# Power_Regulation.net
KiCad netlist of a schematic drawn in Altium Designer
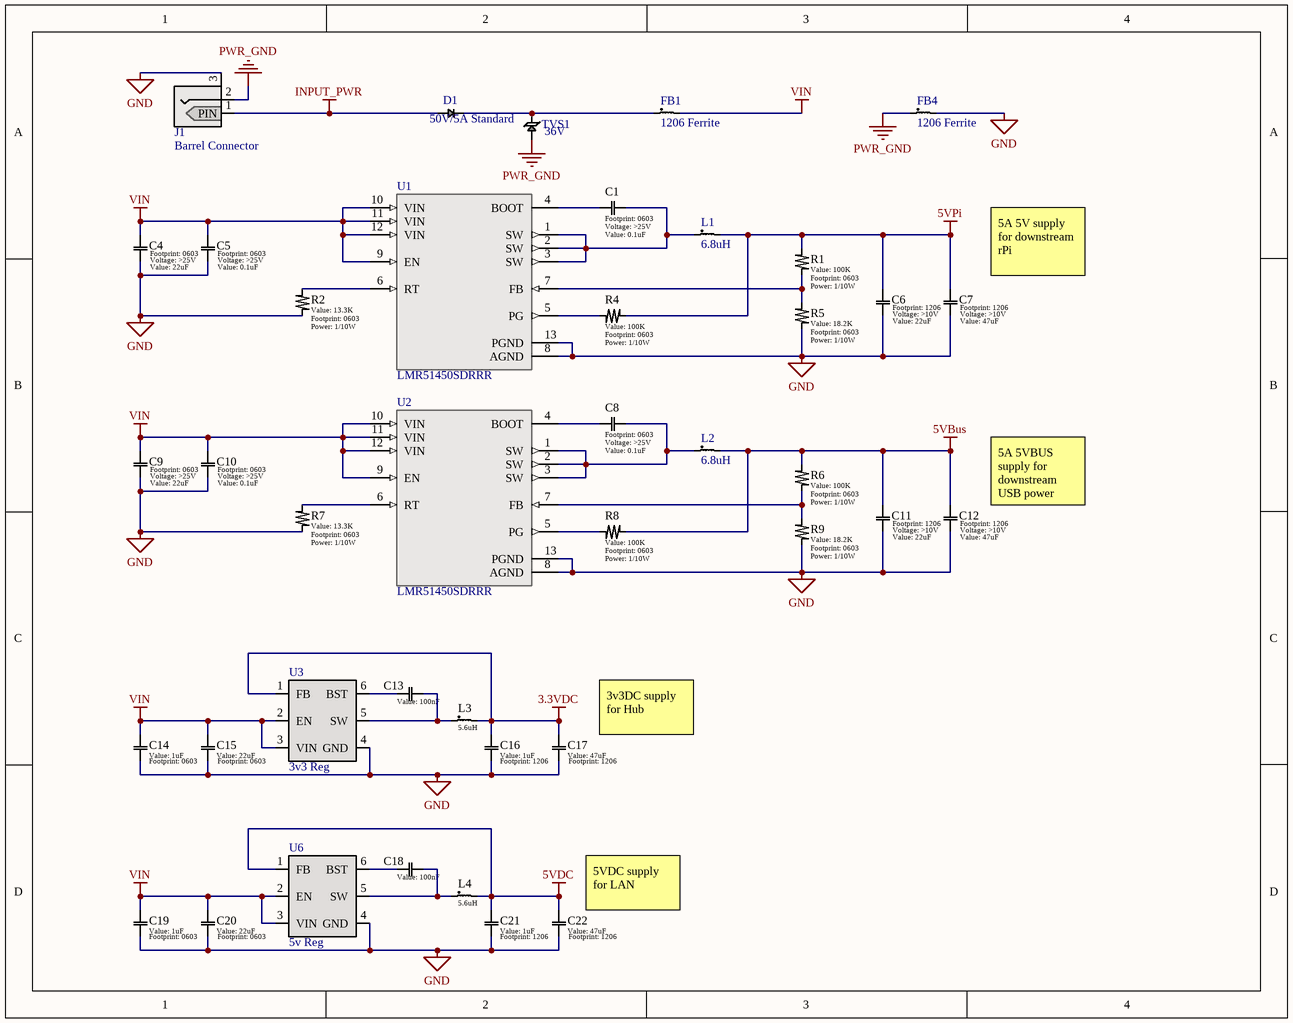
[diagram p0: Power Regulation.SchDoc]

(export (version "E")
  (design (tool "Eeschema 10.0.6"))
  (components
    (comp (ref "C1")
      (value "0.1uF")
      (footprint "0603")
      (fields
        (field (name "VOLTAGE") ">25V")
        (field (name "TOLERANCE") "10%")
        (field (name "Comment") "Generic Capacitor")
      )
      (libsource (lib "Capacitors") (part "Generic Capacitor"))
    )
    (comp (ref "C4")
      (value "22uF")
      (footprint "0603")
      (fields
        (field (name "VOLTAGE") ">25V")
        (field (name "TOLERANCE") "10%")
        (field (name "Comment") "Generic Capacitor")
      )
      (libsource (lib "Capacitors") (part "Generic Capacitor"))
    )
    (comp (ref "C5")
      (value "0.1uF")
      (footprint "0603")
      (fields
        (field (name "VOLTAGE") ">25V")
        (field (name "TOLERANCE") "10%")
        (field (name "Comment") "Generic Capacitor")
      )
      (libsource (lib "Capacitors") (part "Generic Capacitor"))
    )
    (comp (ref "C6")
      (value "22uF")
      (footprint "1206")
      (fields
        (field (name "VOLTAGE") ">10V")
        (field (name "TOLERANCE") "20%")
        (field (name "Comment") "Generic Capacitor")
      )
      (libsource (lib "Capacitors") (part "Generic Capacitor"))
    )
    (comp (ref "C7")
      (value "47uF")
      (footprint "1206")
      (fields
        (field (name "VOLTAGE") ">10V")
        (field (name "TOLERANCE") "10%")
        (field (name "Comment") "Generic Capacitor")
      )
      (libsource (lib "Capacitors") (part "Generic Capacitor"))
    )
    (comp (ref "C8")
      (value "0.1uF")
      (footprint "0603")
      (fields
        (field (name "VOLTAGE") ">25V")
        (field (name "TOLERANCE") "10%")
        (field (name "Comment") "Generic Capacitor")
      )
      (libsource (lib "Capacitors") (part "Generic Capacitor"))
    )
    (comp (ref "C9")
      (value "22uF")
      (footprint "0603")
      (fields
        (field (name "VOLTAGE") ">25V")
        (field (name "TOLERANCE") "10%")
        (field (name "Comment") "Generic Capacitor")
      )
      (libsource (lib "Capacitors") (part "Generic Capacitor"))
    )
    (comp (ref "C10")
      (value "0.1uF")
      (footprint "0603")
      (fields
        (field (name "VOLTAGE") ">25V")
        (field (name "TOLERANCE") "10%")
        (field (name "Comment") "Generic Capacitor")
      )
      (libsource (lib "Capacitors") (part "Generic Capacitor"))
    )
    (comp (ref "C11")
      (value "22uF")
      (footprint "1206")
      (fields
        (field (name "VOLTAGE") ">10V")
        (field (name "TOLERANCE") "20%")
        (field (name "Comment") "Generic Capacitor")
      )
      (libsource (lib "Capacitors") (part "Generic Capacitor"))
    )
    (comp (ref "C12")
      (value "47uF")
      (footprint "1206")
      (fields
        (field (name "VOLTAGE") ">10V")
        (field (name "TOLERANCE") "10%")
        (field (name "Comment") "Generic Capacitor")
      )
      (libsource (lib "Capacitors") (part "Generic Capacitor"))
    )
    (comp (ref "C13")
      (value "100nF")
      (footprint "0603")
      (fields
        (field (name "VOLTAGE") ">10V")
        (field (name "TOLERANCE") "10%")
        (field (name "Comment") "Generic Capacitor")
      )
      (libsource (lib "Capacitors") (part "Generic Capacitor"))
    )
    (comp (ref "C14")
      (value "1uF")
      (footprint "0603")
      (fields
        (field (name "VOLTAGE") ">10V")
        (field (name "TOLERANCE") "10%")
        (field (name "Comment") "Generic Capacitor")
      )
      (libsource (lib "Capacitors") (part "Generic Capacitor"))
    )
    (comp (ref "C15")
      (value "22uF")
      (footprint "0603")
      (fields
        (field (name "VOLTAGE") ">10V")
        (field (name "TOLERANCE") "10%")
        (field (name "Comment") "Generic Capacitor")
      )
      (libsource (lib "Capacitors") (part "Generic Capacitor"))
    )
    (comp (ref "C16")
      (value "1uF")
      (footprint "1206")
      (fields
        (field (name "VOLTAGE") ">10V")
        (field (name "TOLERANCE") "10%")
        (field (name "Comment") "Generic Capacitor")
      )
      (libsource (lib "Capacitors") (part "Generic Capacitor"))
    )
    (comp (ref "C17")
      (value "47uF")
      (footprint "1206")
      (fields
        (field (name "VOLTAGE") ">10V")
        (field (name "TOLERANCE") "10%")
        (field (name "Comment") "Generic Capacitor")
      )
      (libsource (lib "Capacitors") (part "Generic Capacitor"))
    )
    (comp (ref "C18")
      (value "100nF")
      (footprint "0603")
      (fields
        (field (name "VOLTAGE") ">10V")
        (field (name "TOLERANCE") "10%")
        (field (name "Comment") "Generic Capacitor")
      )
      (libsource (lib "Capacitors") (part "Generic Capacitor"))
    )
    (comp (ref "C19")
      (value "1uF")
      (footprint "0603")
      (fields
        (field (name "VOLTAGE") ">10V")
        (field (name "TOLERANCE") "10%")
        (field (name "Comment") "Generic Capacitor")
      )
      (libsource (lib "Capacitors") (part "Generic Capacitor"))
    )
    (comp (ref "C20")
      (value "22uF")
      (footprint "0603")
      (fields
        (field (name "VOLTAGE") ">10V")
        (field (name "TOLERANCE") "10%")
        (field (name "Comment") "Generic Capacitor")
      )
      (libsource (lib "Capacitors") (part "Generic Capacitor"))
    )
    (comp (ref "C21")
      (value "1uF")
      (footprint "1206")
      (fields
        (field (name "VOLTAGE") ">10V")
        (field (name "TOLERANCE") "10%")
        (field (name "Comment") "Generic Capacitor")
      )
      (libsource (lib "Capacitors") (part "Generic Capacitor"))
    )
    (comp (ref "C22")
      (value "47uF")
      (footprint "1206")
      (fields
        (field (name "VOLTAGE") ">10V")
        (field (name "TOLERANCE") "10%")
        (field (name "Comment") "Generic Capacitor")
      )
      (libsource (lib "Capacitors") (part "Generic Capacitor"))
    )
    (comp (ref "D1")
      (value "50V/5A Standard")
      (footprint "DO-214AC")
      (description "Diode Super Barrier 50V 5A Surface Mount")
      (libsource (lib "Diodes") (part "SBRT5A50SA-13"))
    )
    (comp (ref "FB1")
      (value "1206 Ferrite")
      (footprint "1206")
      (description "160 Ohms @ 100MHz 1 Power, Signal Line Ferrite Bead 1206 (3216 Metric) 6A 18mOhm")
      (libsource (lib "Inductors") (part "HI1206T161R-10"))
    )
    (comp (ref "FB4")
      (value "1206 Ferrite")
      (footprint "1206")
      (description "160 Ohms @ 100MHz 1 Power, Signal Line Ferrite Bead 1206 (3216 Metric) 6A 18mOhm")
      (libsource (lib "Inductors") (part "HI1206T161R-10"))
    )
    (comp (ref "J1")
      (value "Barrel Connector")
      (footprint "PJ-082BH")
      (description "CONN PWR JACK 2.5X5.5MM SOLDER")
      (libsource (lib "Connectors") (part "PJ-082BH"))
    )
    (comp (ref "L1")
      (value "6.8uH")
      (footprint "IHLP3232DZER6R8M11")
      (description "FIXED IND 6.8UH 7A 33.4 MOHM SMD")
      (fields (field (name "TOLERANCE") "20%") (field (name "INDUCTANCE") "6.8uH"))
      (libsource (lib "Inductors") (part "IHLP3232DZER6R8M11"))
    )
    (comp (ref "L2")
      (value "6.8uH")
      (footprint "IHLP3232DZER6R8M11")
      (description "FIXED IND 6.8UH 7A 33.4 MOHM SMD")
      (fields (field (name "TOLERANCE") "20%") (field (name "INDUCTANCE") "6.8uH"))
      (libsource (lib "Inductors") (part "IHLP3232DZER6R8M11"))
    )
    (comp (ref "L3")
      (value "5.6uH")
      (footprint "TMPC0402HP")
      (description "2A 5.6uH ±20% SMD Power Inductor")
      (libsource (lib "Inductors") (part "TMPC0402HP-5R6MG-Z02"))
    )
    (comp (ref "L4")
      (value "5.6uH")
      (footprint "TMPC0402HP")
      (description "2A 5.6uH ±20% SMD Power Inductor")
      (libsource (lib "Inductors") (part "TMPC0402HP-5R6MG-Z02"))
    )
    (comp (ref "R1")
      (value "100K")
      (footprint "0603")
      (fields
        (field (name "TOLERANCE") "1%")
        (field (name "POWER") "1/10W")
        (field (name "Comment") "Generic Resistor")
      )
      (libsource (lib "Resistors") (part "Generic Resistor"))
    )
    (comp (ref "R2")
      (value "13.3K")
      (footprint "0603")
      (fields
        (field (name "TOLERANCE") "1%")
        (field (name "POWER") "1/10W")
        (field (name "Comment") "Generic Resistor")
      )
      (libsource (lib "Resistors") (part "Generic Resistor"))
    )
    (comp (ref "R4")
      (value "100K")
      (footprint "0603")
      (fields
        (field (name "TOLERANCE") "1%")
        (field (name "POWER") "1/10W")
        (field (name "Comment") "Generic Resistor")
      )
      (libsource (lib "Resistors") (part "Generic Resistor"))
    )
    (comp (ref "R5")
      (value "18.2K")
      (footprint "0603")
      (fields
        (field (name "TOLERANCE") "1%")
        (field (name "POWER") "1/10W")
        (field (name "Comment") "Generic Resistor")
      )
      (libsource (lib "Resistors") (part "Generic Resistor"))
    )
    (comp (ref "R6")
      (value "100K")
      (footprint "0603")
      (fields
        (field (name "TOLERANCE") "1%")
        (field (name "POWER") "1/10W")
        (field (name "Comment") "Generic Resistor")
      )
      (libsource (lib "Resistors") (part "Generic Resistor"))
    )
    (comp (ref "R7")
      (value "13.3K")
      (footprint "0603")
      (fields
        (field (name "TOLERANCE") "1%")
        (field (name "POWER") "1/10W")
        (field (name "Comment") "Generic Resistor")
      )
      (libsource (lib "Resistors") (part "Generic Resistor"))
    )
    (comp (ref "R8")
      (value "100K")
      (footprint "0603")
      (fields
        (field (name "TOLERANCE") "1%")
        (field (name "POWER") "1/10W")
        (field (name "Comment") "Generic Resistor")
      )
      (libsource (lib "Resistors") (part "Generic Resistor"))
    )
    (comp (ref "R9")
      (value "18.2K")
      (footprint "0603")
      (fields
        (field (name "TOLERANCE") "1%")
        (field (name "POWER") "1/10W")
        (field (name "Comment") "Generic Resistor")
      )
      (libsource (lib "Resistors") (part "Generic Resistor"))
    )
    (comp (ref "TVS1")
      (value "36V")
      (footprint "DO-214AC")
      (description "58.1V Clamp 6.9A Ipp Tvs Diode Surface Mount DO-214AC (SMA)")
      (libsource (lib "Diodes") (part "SMAJ36A"))
    )
    (comp (ref "U1")
      (value "LMR51450SDRRR")
      (footprint "WSON-12")
      (description "36-V, 5-A synchronous buck converter")
      (fields (field (name "MF") "Texas Instruments"))
      (libsource (lib "Regulators") (part "LMR51450SDRRR"))
    )
    (comp (ref "U2")
      (value "LMR51450SDRRR")
      (footprint "WSON-12")
      (description "36-V, 5-A synchronous buck converter")
      (fields (field (name "MF") "Texas Instruments"))
      (libsource (lib "Regulators") (part "LMR51450SDRRR"))
    )
    (comp (ref "U3")
      (value "3v3 Reg")
      (footprint "TSOT-23-6")
      (description "Switching Voltage Regulators DCDC Conv HV Buck TSOT26 T&R 3K")
      (fields
        (field (name "MANUFACTURER_PART_NUMBER") "AP63203WU-7")
        (field (name "MOUSER PART NUMBER") "621-AP63203WU-7")
      )
      (libsource (lib "Regulators") (part "AP63203WU-7"))
    )
    (comp (ref "U6")
      (value "5v Reg")
      (footprint "TSOT-23-6")
      (description "Step-down type Fixed 2A 5V 3.8V~32V")
      (fields
        (field (name "MANUFACTURER_PART_NUMBER") "AP63205WU-7")
        (field (name "COPYRIGHT") "Copyright (C) 2023 Ultra Librarian. All rights reserved.")
      )
      (libsource (lib "Regulators") (part "AP63205WU-7"))
    )
  )
  (nets
    (net (code "1") (name "3.3VDC") (class "Default")
      (node (ref "C16") (pin "1") (pinfunction "1_1") (pintype "passive"))
      (node (ref "C17") (pin "1") (pinfunction "1_1") (pintype "passive"))
      (node (ref "L3") (pin "2") (pinfunction "2_2") (pintype "passive"))
      (node (ref "U3") (pin "1") (pinfunction "FB_1") (pintype "passive"))
    )
    (net (code "2") (name "5VBus") (class "Default")
      (node (ref "C11") (pin "1") (pinfunction "1_1") (pintype "passive"))
      (node (ref "C12") (pin "1") (pinfunction "1_1") (pintype "passive"))
      (node (ref "L2") (pin "2") (pinfunction "2_2") (pintype "passive"))
      (node (ref "R6") (pin "2") (pinfunction "2_2") (pintype "passive"))
      (node (ref "R8") (pin "1") (pinfunction "1_1") (pintype "passive"))
    )
    (net (code "3") (name "5VDC") (class "Default")
      (node (ref "C21") (pin "1") (pinfunction "1_1") (pintype "passive"))
      (node (ref "C22") (pin "1") (pinfunction "1_1") (pintype "passive"))
      (node (ref "L4") (pin "2") (pinfunction "2_2") (pintype "passive"))
      (node (ref "U6") (pin "1") (pinfunction "FB_1") (pintype "passive"))
    )
    (net (code "4") (name "5VPi") (class "Default")
      (node (ref "C6") (pin "1") (pinfunction "1_1") (pintype "passive"))
      (node (ref "C7") (pin "1") (pinfunction "1_1") (pintype "passive"))
      (node (ref "L1") (pin "2") (pinfunction "2_2") (pintype "passive"))
      (node (ref "R1") (pin "2") (pinfunction "2_2") (pintype "passive"))
      (node (ref "R4") (pin "1") (pinfunction "1_1") (pintype "passive"))
    )
    (net (code "5") (name "GND") (class "Default")
      (node (ref "C10") (pin "2") (pinfunction "2_2") (pintype "passive"))
      (node (ref "C11") (pin "2") (pinfunction "2_2") (pintype "passive"))
      (node (ref "C12") (pin "2") (pinfunction "2_2") (pintype "passive"))
      (node (ref "C14") (pin "2") (pinfunction "2_2") (pintype "passive"))
      (node (ref "C15") (pin "2") (pinfunction "2_2") (pintype "passive"))
      (node (ref "C16") (pin "2") (pinfunction "2_2") (pintype "passive"))
      (node (ref "C17") (pin "2") (pinfunction "2_2") (pintype "passive"))
      (node (ref "C19") (pin "2") (pinfunction "2_2") (pintype "passive"))
      (node (ref "C20") (pin "2") (pinfunction "2_2") (pintype "passive"))
      (node (ref "C21") (pin "2") (pinfunction "2_2") (pintype "passive"))
      (node (ref "C22") (pin "2") (pinfunction "2_2") (pintype "passive"))
      (node (ref "C4") (pin "2") (pinfunction "2_2") (pintype "passive"))
      (node (ref "C5") (pin "2") (pinfunction "2_2") (pintype "passive"))
      (node (ref "C6") (pin "2") (pinfunction "2_2") (pintype "passive"))
      (node (ref "C7") (pin "2") (pinfunction "2_2") (pintype "passive"))
      (node (ref "C9") (pin "2") (pinfunction "2_2") (pintype "passive"))
      (node (ref "FB4") (pin "2") (pinfunction "2_2") (pintype "passive"))
      (node (ref "J1") (pin "3") (pinfunction "SHD_B_3") (pintype "passive"))
      (node (ref "R2") (pin "1") (pinfunction "1_1") (pintype "passive"))
      (node (ref "R5") (pin "1") (pinfunction "1_1") (pintype "passive"))
      (node (ref "R7") (pin "1") (pinfunction "1_1") (pintype "passive"))
      (node (ref "R9") (pin "1") (pinfunction "1_1") (pintype "passive"))
      (node (ref "U1") (pin "13") (pinfunction "PGND_13") (pintype "power_in"))
      (node (ref "U1") (pin "8") (pinfunction "AGND_8") (pintype "power_in"))
      (node (ref "U2") (pin "13") (pinfunction "PGND_13") (pintype "power_in"))
      (node (ref "U2") (pin "8") (pinfunction "AGND_8") (pintype "power_in"))
      (node (ref "U3") (pin "4") (pinfunction "GND_4") (pintype "power_in"))
      (node (ref "U6") (pin "4") (pinfunction "GND_4") (pintype "power_in"))
    )
    (net (code "6") (name "INPUT_PWR") (class "Default")
      (node (ref "D1") (pin "2") (pinfunction "Anode_2") (pintype "passive"))
      (node (ref "J1") (pin "1") (pinfunction "PIN_1") (pintype "passive"))
    )
    (net (code "7") (name "Net-(C1-Pad2)") (class "Default")
      (node (ref "C1") (pin "2") (pinfunction "2_2") (pintype "passive"))
      (node (ref "L1") (pin "1") (pinfunction "1_1") (pintype "passive"))
      (node (ref "U1") (pin "1") (pinfunction "SW_1") (pintype "output"))
      (node (ref "U1") (pin "2") (pinfunction "SW_2") (pintype "output"))
      (node (ref "U1") (pin "3") (pinfunction "SW_3") (pintype "output"))
    )
    (net (code "8") (name "Net-(C8-Pad2)") (class "Default")
      (node (ref "C8") (pin "2") (pinfunction "2_2") (pintype "passive"))
      (node (ref "L2") (pin "1") (pinfunction "1_1") (pintype "passive"))
      (node (ref "U2") (pin "1") (pinfunction "SW_1") (pintype "output"))
      (node (ref "U2") (pin "2") (pinfunction "SW_2") (pintype "output"))
      (node (ref "U2") (pin "3") (pinfunction "SW_3") (pintype "output"))
    )
    (net (code "9") (name "Net-(D1-Cathode)") (class "Default")
      (node (ref "D1") (pin "1") (pinfunction "Cathode_1") (pintype "passive"))
      (node (ref "FB1") (pin "1") (pinfunction "1_1") (pintype "passive"))
      (node (ref "TVS1") (pin "1") (pinfunction "Cathode_1") (pintype "passive"))
    )
    (net (code "10") (name "Net-(U1-BOOT)") (class "Default")
      (node (ref "C1") (pin "1") (pinfunction "1_1") (pintype "passive"))
      (node (ref "U1") (pin "4") (pinfunction "BOOT_4") (pintype "passive"))
    )
    (net (code "11") (name "Net-(U1-FB)") (class "Default")
      (node (ref "R1") (pin "1") (pinfunction "1_1") (pintype "passive"))
      (node (ref "R5") (pin "2") (pinfunction "2_2") (pintype "passive"))
      (node (ref "U1") (pin "7") (pinfunction "FB_7") (pintype "input"))
    )
    (net (code "12") (name "Net-(U1-PG)") (class "Default")
      (node (ref "R4") (pin "2") (pinfunction "2_2") (pintype "passive"))
      (node (ref "U1") (pin "5") (pinfunction "PG_5") (pintype "output"))
    )
    (net (code "13") (name "Net-(U1-RT)") (class "Default")
      (node (ref "R2") (pin "2") (pinfunction "2_2") (pintype "passive"))
      (node (ref "U1") (pin "6") (pinfunction "RT_6") (pintype "input"))
    )
    (net (code "14") (name "Net-(U2-BOOT)") (class "Default")
      (node (ref "C8") (pin "1") (pinfunction "1_1") (pintype "passive"))
      (node (ref "U2") (pin "4") (pinfunction "BOOT_4") (pintype "passive"))
    )
    (net (code "15") (name "Net-(U2-FB)") (class "Default")
      (node (ref "R6") (pin "1") (pinfunction "1_1") (pintype "passive"))
      (node (ref "R9") (pin "2") (pinfunction "2_2") (pintype "passive"))
      (node (ref "U2") (pin "7") (pinfunction "FB_7") (pintype "input"))
    )
    (net (code "16") (name "Net-(U2-PG)") (class "Default")
      (node (ref "R8") (pin "2") (pinfunction "2_2") (pintype "passive"))
      (node (ref "U2") (pin "5") (pinfunction "PG_5") (pintype "output"))
    )
    (net (code "17") (name "Net-(U2-RT)") (class "Default")
      (node (ref "R7") (pin "2") (pinfunction "2_2") (pintype "passive"))
      (node (ref "U2") (pin "6") (pinfunction "RT_6") (pintype "input"))
    )
    (net (code "18") (name "Net-(U3-BST)") (class "Default")
      (node (ref "C13") (pin "1") (pinfunction "1_1") (pintype "passive"))
      (node (ref "U3") (pin "6") (pinfunction "BST_6") (pintype "passive"))
    )
    (net (code "19") (name "Net-(U3-SW)") (class "Default")
      (node (ref "C13") (pin "2") (pinfunction "2_2") (pintype "passive"))
      (node (ref "L3") (pin "1") (pinfunction "1_1") (pintype "passive"))
      (node (ref "U3") (pin "5") (pinfunction "SW_5") (pintype "passive"))
    )
    (net (code "20") (name "Net-(U6-BST)") (class "Default")
      (node (ref "C18") (pin "1") (pinfunction "1_1") (pintype "passive"))
      (node (ref "U6") (pin "6") (pinfunction "BST_6") (pintype "passive"))
    )
    (net (code "21") (name "Net-(U6-SW)") (class "Default")
      (node (ref "C18") (pin "2") (pinfunction "2_2") (pintype "passive"))
      (node (ref "L4") (pin "1") (pinfunction "1_1") (pintype "passive"))
      (node (ref "U6") (pin "5") (pinfunction "SW_5") (pintype "passive"))
    )
    (net (code "22") (name "PWR_GND") (class "Default")
      (node (ref "FB4") (pin "1") (pinfunction "1_1") (pintype "passive"))
      (node (ref "J1") (pin "2") (pinfunction "SHD_A_2") (pintype "passive"))
      (node (ref "TVS1") (pin "2") (pinfunction "Anode_2") (pintype "passive"))
    )
    (net (code "23") (name "VIN") (class "Default")
      (node (ref "C10") (pin "1") (pinfunction "1_1") (pintype "passive"))
      (node (ref "C14") (pin "1") (pinfunction "1_1") (pintype "passive"))
      (node (ref "C15") (pin "1") (pinfunction "1_1") (pintype "passive"))
      (node (ref "C19") (pin "1") (pinfunction "1_1") (pintype "passive"))
      (node (ref "C20") (pin "1") (pinfunction "1_1") (pintype "passive"))
      (node (ref "C4") (pin "1") (pinfunction "1_1") (pintype "passive"))
      (node (ref "C5") (pin "1") (pinfunction "1_1") (pintype "passive"))
      (node (ref "C9") (pin "1") (pinfunction "1_1") (pintype "passive"))
      (node (ref "FB1") (pin "2") (pinfunction "2_2") (pintype "passive"))
      (node (ref "U1") (pin "10") (pinfunction "VIN_10") (pintype "input"))
      (node (ref "U1") (pin "11") (pinfunction "VIN_11") (pintype "input"))
      (node (ref "U1") (pin "12") (pinfunction "VIN_12") (pintype "input"))
      (node (ref "U1") (pin "9") (pinfunction "EN_9") (pintype "input"))
      (node (ref "U2") (pin "10") (pinfunction "VIN_10") (pintype "input"))
      (node (ref "U2") (pin "11") (pinfunction "VIN_11") (pintype "input"))
      (node (ref "U2") (pin "12") (pinfunction "VIN_12") (pintype "input"))
      (node (ref "U2") (pin "9") (pinfunction "EN_9") (pintype "input"))
      (node (ref "U3") (pin "2") (pinfunction "EN_2") (pintype "passive"))
      (node (ref "U3") (pin "3") (pinfunction "VIN_3") (pintype "passive"))
      (node (ref "U6") (pin "2") (pinfunction "EN_2") (pintype "passive"))
      (node (ref "U6") (pin "3") (pinfunction "VIN_3") (pintype "passive"))
    )
  )
)
